# Paddidle_FrontPannel.net
KiCad netlist of a schematic drawn in EAGLE
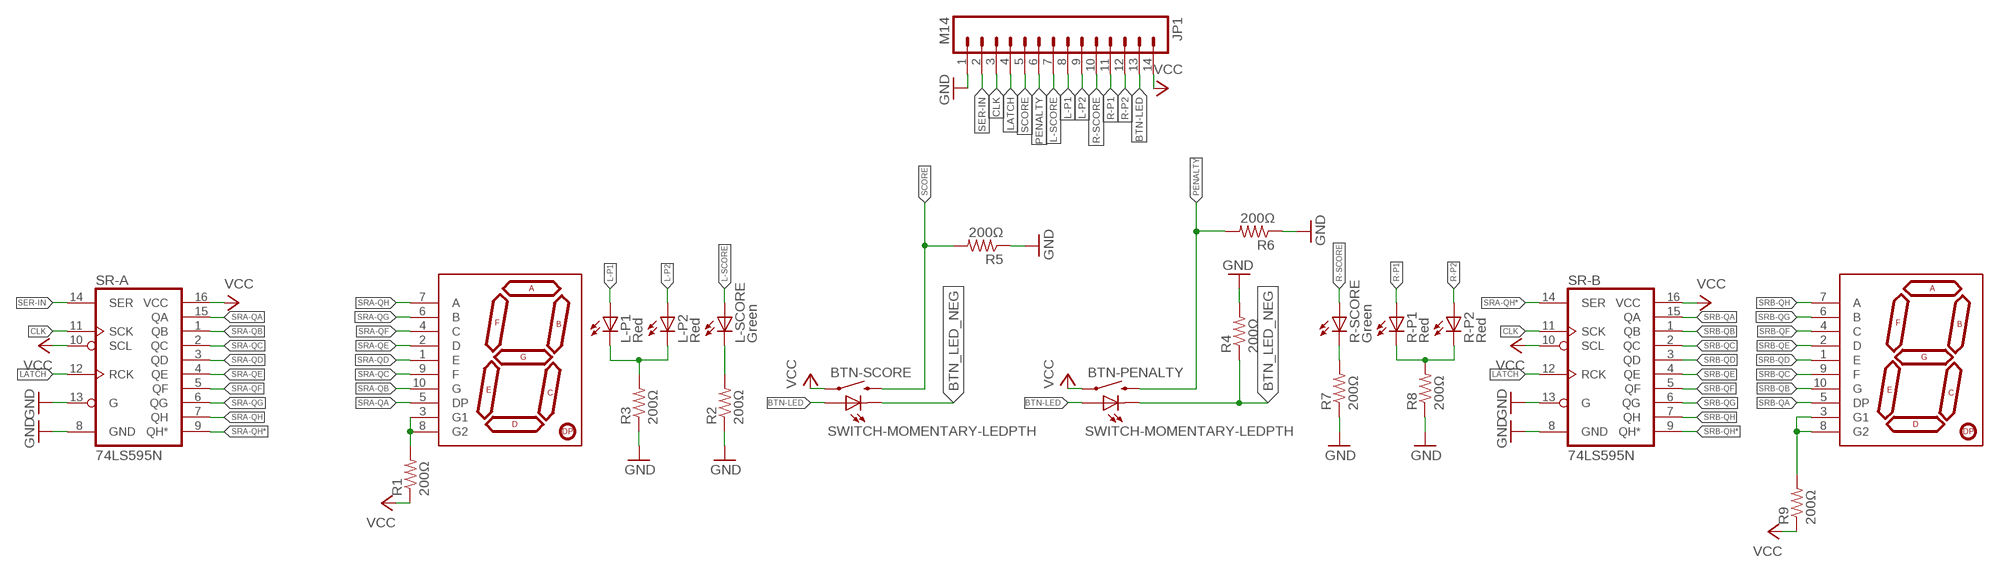
[diagram p0: schematic, sheet 1]

(export (version "E")
  (design (tool "Eeschema 10.0.6"))
  (components
    (comp (ref "7SEG-L")
      (value "7-SEGMENT-DISPLAY-1\"-RED")
      (footprint "eagle-import:7-SEGMENT-1_PTH")
      (libsource (lib "eagle-import") (part "7-SEGMENT-DISPLAY-1{dblquote}-RED"))
    )
    (comp (ref "7SEG-R")
      (value "7-SEGMENT-DISPLAY-1\"-RED")
      (footprint "eagle-import:7-SEGMENT-1_PTH")
      (libsource (lib "eagle-import") (part "7-SEGMENT-DISPLAY-1{dblquote}-RED"))
    )
    (comp (ref "BTN-PENALTY")
      (value "SWITCH-MOMENTARY-LEDPTH")
      (footprint "eagle-import:TACTILE-PTH-LED-12MM")
      (libsource (lib "eagle-import") (part "SWITCH-MOMENTARY-LEDPTH"))
    )
    (comp (ref "BTN-SCORE")
      (value "SWITCH-MOMENTARY-LEDPTH")
      (footprint "eagle-import:TACTILE-PTH-LED-12MM")
      (libsource (lib "eagle-import") (part "SWITCH-MOMENTARY-LEDPTH"))
    )
    (comp (ref "JP1")
      (value "M14")
      (footprint "eagle-import:1X14")
      (libsource (lib "eagle-import") (part "M14"))
    )
    (comp (ref "L-P1")
      (value "Red")
      (footprint "eagle-import:LED5MM")
      (libsource (lib "eagle-import") (part "LED5MM"))
    )
    (comp (ref "L-P2")
      (value "Red")
      (footprint "eagle-import:LED5MM")
      (libsource (lib "eagle-import") (part "LED5MM"))
    )
    (comp (ref "L-SCORE")
      (value "Green")
      (footprint "eagle-import:LED5MM")
      (libsource (lib "eagle-import") (part "LED5MM"))
    )
    (comp (ref "R-P1")
      (value "Red")
      (footprint "eagle-import:LED5MM")
      (libsource (lib "eagle-import") (part "LED5MM"))
    )
    (comp (ref "R-P2")
      (value "Red")
      (footprint "eagle-import:LED5MM")
      (libsource (lib "eagle-import") (part "LED5MM"))
    )
    (comp (ref "R-SCORE")
      (value "Green")
      (footprint "eagle-import:LED5MM")
      (libsource (lib "eagle-import") (part "LED5MM"))
    )
    (comp (ref "R1")
      (value "200Ω")
      (footprint "eagle-import:R0805")
      (fields (field (name "MPN") "PFC-W0805LF-03-2000-B"))
      (libsource (lib "eagle-import") (part "R-US_R0805"))
    )
    (comp (ref "R2")
      (value "200Ω")
      (footprint "eagle-import:R0805")
      (fields (field (name "MPN") "PFC-W0805LF-03-2000-B"))
      (libsource (lib "eagle-import") (part "R-US_R0805"))
    )
    (comp (ref "R3")
      (value "200Ω")
      (footprint "eagle-import:R0805")
      (fields (field (name "MPN") "PFC-W0805LF-03-2000-B"))
      (libsource (lib "eagle-import") (part "R-US_R0805"))
    )
    (comp (ref "R4")
      (value "200Ω")
      (footprint "eagle-import:R0805")
      (fields (field (name "MPN") "PFC-W0805LF-03-2000-B"))
      (libsource (lib "eagle-import") (part "R-US_R0805"))
    )
    (comp (ref "R5")
      (value "200Ω")
      (footprint "eagle-import:R0805")
      (fields (field (name "MPN") "PFC-W0805LF-03-2000-B"))
      (libsource (lib "eagle-import") (part "R-US_R0805"))
    )
    (comp (ref "R6")
      (value "200Ω")
      (footprint "eagle-import:R0805")
      (fields (field (name "MPN") "PFC-W0805LF-03-2000-B"))
      (libsource (lib "eagle-import") (part "R-US_R0805"))
    )
    (comp (ref "R7")
      (value "200Ω")
      (footprint "eagle-import:R0805")
      (fields (field (name "MPN") "PFC-W0805LF-03-2000-B"))
      (libsource (lib "eagle-import") (part "R-US_R0805"))
    )
    (comp (ref "R8")
      (value "200Ω")
      (footprint "eagle-import:R0805")
      (fields (field (name "MPN") "PFC-W0805LF-03-2000-B"))
      (libsource (lib "eagle-import") (part "R-US_R0805"))
    )
    (comp (ref "R9")
      (value "200Ω")
      (footprint "eagle-import:R0805")
      (fields (field (name "MPN") "PFC-W0805LF-03-2000-B"))
      (libsource (lib "eagle-import") (part "R-US_R0805"))
    )
    (comp (ref "SR-A")
      (value "74LS595N")
      (footprint "eagle-import:DIL16")
      (fields (field (name "MF") "TEXAS INSTRUMENTS") (field (name "MPN") "SN74LS595N"))
      (libsource (lib "eagle-import") (part "74595NLS"))
    )
    (comp (ref "SR-B")
      (value "74LS595N")
      (footprint "eagle-import:DIL16")
      (fields (field (name "MF") "TEXAS INSTRUMENTS") (field (name "MPN") "SN74LS595N"))
      (libsource (lib "eagle-import") (part "74595NLS"))
    )
  )
  (nets
    (net (code "1") (name "BTN-LED") (class "Default")
      (node (ref "BTN-PENALTY") (pin "A") (pinfunction "A_A") (pintype "passive"))
      (node (ref "BTN-SCORE") (pin "A") (pinfunction "A_A") (pintype "passive"))
      (node (ref "JP1") (pin "13") (pinfunction "13_13") (pintype "passive"))
    )
    (net (code "2") (name "BTN_LED_NEG") (class "Default")
      (node (ref "BTN-PENALTY") (pin "C") (pinfunction "C_C") (pintype "passive"))
      (node (ref "BTN-SCORE") (pin "C") (pinfunction "C_C") (pintype "passive"))
      (node (ref "R4") (pin "1") (pinfunction "1_1") (pintype "passive"))
    )
    (net (code "3") (name "CLK") (class "Default")
      (node (ref "JP1") (pin "3") (pinfunction "3_3") (pintype "passive"))
      (node (ref "SR-A") (pin "11") (pinfunction "SCK_11") (pintype "input"))
      (node (ref "SR-B") (pin "11") (pinfunction "SCK_11") (pintype "input"))
    )
    (net (code "4") (name "GND") (class "Default")
      (node (ref "JP1") (pin "1") (pinfunction "1_1") (pintype "passive"))
      (node (ref "R2") (pin "1") (pinfunction "1_1") (pintype "passive"))
      (node (ref "R3") (pin "1") (pinfunction "1_1") (pintype "passive"))
      (node (ref "R4") (pin "2") (pinfunction "2_2") (pintype "passive"))
      (node (ref "R5") (pin "1") (pinfunction "1_1") (pintype "passive"))
      (node (ref "R6") (pin "1") (pinfunction "1_1") (pintype "passive"))
      (node (ref "R7") (pin "1") (pinfunction "1_1") (pintype "passive"))
      (node (ref "R8") (pin "1") (pinfunction "1_1") (pintype "passive"))
      (node (ref "SR-A") (pin "13") (pinfunction "G_13") (pintype "input"))
      (node (ref "SR-A") (pin "8") (pinfunction "GND_8") (pintype "power_in"))
      (node (ref "SR-B") (pin "13") (pinfunction "G_13") (pintype "input"))
      (node (ref "SR-B") (pin "8") (pinfunction "GND_8") (pintype "power_in"))
    )
    (net (code "5") (name "L-P1") (class "Default")
      (node (ref "JP1") (pin "8") (pinfunction "8_8") (pintype "passive"))
      (node (ref "L-P1") (pin "A") (pinfunction "A_A") (pintype "passive"))
    )
    (net (code "6") (name "L-P2") (class "Default")
      (node (ref "JP1") (pin "9") (pinfunction "9_9") (pintype "passive"))
      (node (ref "L-P2") (pin "A") (pinfunction "A_A") (pintype "passive"))
    )
    (net (code "7") (name "L-SCORE") (class "Default")
      (node (ref "JP1") (pin "7") (pinfunction "7_7") (pintype "passive"))
      (node (ref "L-SCORE") (pin "A") (pinfunction "A_A") (pintype "passive"))
    )
    (net (code "8") (name "LATCH") (class "Default")
      (node (ref "JP1") (pin "4") (pinfunction "4_4") (pintype "passive"))
      (node (ref "SR-A") (pin "12") (pinfunction "RCK_12") (pintype "input"))
      (node (ref "SR-B") (pin "12") (pinfunction "RCK_12") (pintype "input"))
    )
    (net (code "9") (name "Net-(7SEG-L-G1)") (class "Default")
      (node (ref "7SEG-L") (pin "3") (pinfunction "G1_3") (pintype "bidirectional"))
      (node (ref "7SEG-L") (pin "8") (pinfunction "G2_8") (pintype "bidirectional"))
      (node (ref "R1") (pin "2") (pinfunction "2_2") (pintype "passive"))
    )
    (net (code "10") (name "Net-(7SEG-R-G1)") (class "Default")
      (node (ref "7SEG-R") (pin "3") (pinfunction "G1_3") (pintype "bidirectional"))
      (node (ref "7SEG-R") (pin "8") (pinfunction "G2_8") (pintype "bidirectional"))
      (node (ref "R9") (pin "2") (pinfunction "2_2") (pintype "passive"))
    )
    (net (code "11") (name "Net-(L-P1-C)") (class "Default")
      (node (ref "L-P1") (pin "K") (pinfunction "C_K") (pintype "passive"))
      (node (ref "L-P2") (pin "K") (pinfunction "C_K") (pintype "passive"))
      (node (ref "R3") (pin "2") (pinfunction "2_2") (pintype "passive"))
    )
    (net (code "12") (name "Net-(L-SCORE-C)") (class "Default")
      (node (ref "L-SCORE") (pin "K") (pinfunction "C_K") (pintype "passive"))
      (node (ref "R2") (pin "2") (pinfunction "2_2") (pintype "passive"))
    )
    (net (code "13") (name "Net-(R-P1-C)") (class "Default")
      (node (ref "R-P1") (pin "K") (pinfunction "C_K") (pintype "passive"))
      (node (ref "R-P2") (pin "K") (pinfunction "C_K") (pintype "passive"))
      (node (ref "R8") (pin "2") (pinfunction "2_2") (pintype "passive"))
    )
    (net (code "14") (name "Net-(R-SCORE-C)") (class "Default")
      (node (ref "R-SCORE") (pin "K") (pinfunction "C_K") (pintype "passive"))
      (node (ref "R7") (pin "2") (pinfunction "2_2") (pintype "passive"))
    )
    (net (code "15") (name "PENALTY") (class "Default")
      (node (ref "BTN-PENALTY") (pin "2") (pinfunction "2_2") (pintype "passive"))
      (node (ref "JP1") (pin "6") (pinfunction "6_6") (pintype "passive"))
      (node (ref "R6") (pin "2") (pinfunction "2_2") (pintype "passive"))
    )
    (net (code "16") (name "R-P1") (class "Default")
      (node (ref "JP1") (pin "11") (pinfunction "11_11") (pintype "passive"))
      (node (ref "R-P1") (pin "A") (pinfunction "A_A") (pintype "passive"))
    )
    (net (code "17") (name "R-P2") (class "Default")
      (node (ref "JP1") (pin "12") (pinfunction "12_12") (pintype "passive"))
      (node (ref "R-P2") (pin "A") (pinfunction "A_A") (pintype "passive"))
    )
    (net (code "18") (name "R-SCORE") (class "Default")
      (node (ref "JP1") (pin "10") (pinfunction "10_10") (pintype "passive"))
      (node (ref "R-SCORE") (pin "A") (pinfunction "A_A") (pintype "passive"))
    )
    (net (code "19") (name "SCORE") (class "Default")
      (node (ref "BTN-SCORE") (pin "2") (pinfunction "2_2") (pintype "passive"))
      (node (ref "JP1") (pin "5") (pinfunction "5_5") (pintype "passive"))
      (node (ref "R5") (pin "2") (pinfunction "2_2") (pintype "passive"))
    )
    (net (code "20") (name "SER-IN") (class "Default")
      (node (ref "JP1") (pin "2") (pinfunction "2_2") (pintype "passive"))
      (node (ref "SR-A") (pin "14") (pinfunction "SER_14") (pintype "input"))
    )
    (net (code "21") (name "SRA-QA") (class "Default")
      (node (ref "7SEG-L") (pin "5") (pinfunction "DP_5") (pintype "bidirectional"))
      (node (ref "SR-A") (pin "15") (pinfunction "QA_15") (pintype "tri_state"))
    )
    (net (code "22") (name "SRA-QB") (class "Default")
      (node (ref "7SEG-L") (pin "10") (pinfunction "G_10") (pintype "bidirectional"))
      (node (ref "SR-A") (pin "1") (pinfunction "QB_1") (pintype "tri_state"))
    )
    (net (code "23") (name "SRA-QC") (class "Default")
      (node (ref "7SEG-L") (pin "9") (pinfunction "F_9") (pintype "bidirectional"))
      (node (ref "SR-A") (pin "2") (pinfunction "QC_2") (pintype "tri_state"))
    )
    (net (code "24") (name "SRA-QD") (class "Default")
      (node (ref "7SEG-L") (pin "1") (pinfunction "E_1") (pintype "bidirectional"))
      (node (ref "SR-A") (pin "3") (pinfunction "QD_3") (pintype "tri_state"))
    )
    (net (code "25") (name "SRA-QE") (class "Default")
      (node (ref "7SEG-L") (pin "2") (pinfunction "D_2") (pintype "bidirectional"))
      (node (ref "SR-A") (pin "4") (pinfunction "QE_4") (pintype "tri_state"))
    )
    (net (code "26") (name "SRA-QF") (class "Default")
      (node (ref "7SEG-L") (pin "4") (pinfunction "C_4") (pintype "bidirectional"))
      (node (ref "SR-A") (pin "5") (pinfunction "QF_5") (pintype "tri_state"))
    )
    (net (code "27") (name "SRA-QG") (class "Default")
      (node (ref "7SEG-L") (pin "6") (pinfunction "B_6") (pintype "bidirectional"))
      (node (ref "SR-A") (pin "6") (pinfunction "QG_6") (pintype "tri_state"))
    )
    (net (code "28") (name "SRA-QH") (class "Default")
      (node (ref "7SEG-L") (pin "7") (pinfunction "A_7") (pintype "bidirectional"))
      (node (ref "SR-A") (pin "7") (pinfunction "QH_7") (pintype "tri_state"))
    )
    (net (code "29") (name "SRA-QH*") (class "Default")
      (node (ref "SR-A") (pin "9") (pinfunction "QH*_9") (pintype "tri_state"))
      (node (ref "SR-B") (pin "14") (pinfunction "SER_14") (pintype "input"))
    )
    (net (code "30") (name "SRB-QA") (class "Default")
      (node (ref "7SEG-R") (pin "5") (pinfunction "DP_5") (pintype "bidirectional"))
      (node (ref "SR-B") (pin "15") (pinfunction "QA_15") (pintype "tri_state"))
    )
    (net (code "31") (name "SRB-QB") (class "Default")
      (node (ref "7SEG-R") (pin "10") (pinfunction "G_10") (pintype "bidirectional"))
      (node (ref "SR-B") (pin "1") (pinfunction "QB_1") (pintype "tri_state"))
    )
    (net (code "32") (name "SRB-QC") (class "Default")
      (node (ref "7SEG-R") (pin "9") (pinfunction "F_9") (pintype "bidirectional"))
      (node (ref "SR-B") (pin "2") (pinfunction "QC_2") (pintype "tri_state"))
    )
    (net (code "33") (name "SRB-QD") (class "Default")
      (node (ref "7SEG-R") (pin "1") (pinfunction "E_1") (pintype "bidirectional"))
      (node (ref "SR-B") (pin "3") (pinfunction "QD_3") (pintype "tri_state"))
    )
    (net (code "34") (name "SRB-QE") (class "Default")
      (node (ref "7SEG-R") (pin "2") (pinfunction "D_2") (pintype "bidirectional"))
      (node (ref "SR-B") (pin "4") (pinfunction "QE_4") (pintype "tri_state"))
    )
    (net (code "35") (name "SRB-QF") (class "Default")
      (node (ref "7SEG-R") (pin "4") (pinfunction "C_4") (pintype "bidirectional"))
      (node (ref "SR-B") (pin "5") (pinfunction "QF_5") (pintype "tri_state"))
    )
    (net (code "36") (name "SRB-QG") (class "Default")
      (node (ref "7SEG-R") (pin "6") (pinfunction "B_6") (pintype "bidirectional"))
      (node (ref "SR-B") (pin "6") (pinfunction "QG_6") (pintype "tri_state"))
    )
    (net (code "37") (name "SRB-QH") (class "Default")
      (node (ref "7SEG-R") (pin "7") (pinfunction "A_7") (pintype "bidirectional"))
      (node (ref "SR-B") (pin "7") (pinfunction "QH_7") (pintype "tri_state"))
    )
    (net (code "38") (name "SRB-QH*") (class "Default")
      (node (ref "SR-B") (pin "9") (pinfunction "QH*_9") (pintype "tri_state"))
    )
    (net (code "39") (name "VCC") (class "Default")
      (node (ref "BTN-PENALTY") (pin "4") (pinfunction "1_4") (pintype "passive"))
      (node (ref "BTN-SCORE") (pin "4") (pinfunction "1_4") (pintype "passive"))
      (node (ref "JP1") (pin "14") (pinfunction "14_14") (pintype "passive"))
      (node (ref "R1") (pin "1") (pinfunction "1_1") (pintype "passive"))
      (node (ref "R9") (pin "1") (pinfunction "1_1") (pintype "passive"))
      (node (ref "SR-A") (pin "10") (pinfunction "SCL_10") (pintype "input"))
      (node (ref "SR-A") (pin "16") (pinfunction "VCC_16") (pintype "power_in"))
      (node (ref "SR-B") (pin "10") (pinfunction "SCL_10") (pintype "input"))
      (node (ref "SR-B") (pin "16") (pinfunction "VCC_16") (pintype "power_in"))
    )
  )
)
